# TinyRFNode84.net
KiCad netlist of a schematic drawn in EAGLE
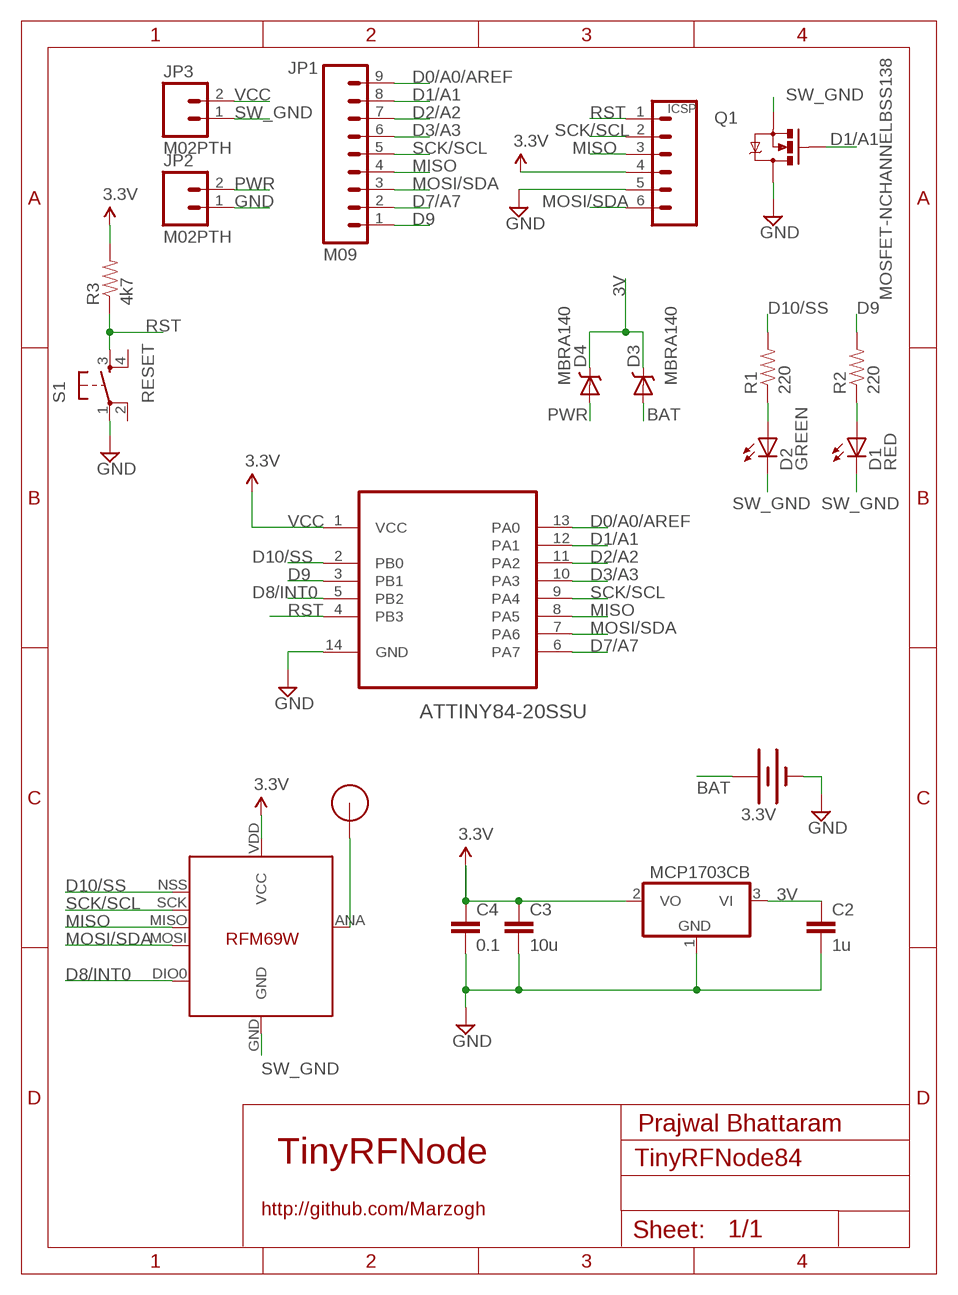
[diagram p0: schematic, sheet 1]

(export (version "E")
  (design (tool "Eeschema 10.0.6"))
  (components
    (comp (ref "BAT1")
      (value "3.3V")
      (footprint "eagle-import:BATTCON_12MM")
      (libsource (lib "eagle-import") (part "BATTERY12MM"))
    )
    (comp (ref "C2")
      (value "1u")
      (footprint "eagle-import:0603-CAP")
      (libsource (lib "eagle-import") (part "CAP0603-CAP"))
    )
    (comp (ref "C3")
      (value "10u")
      (footprint "eagle-import:0805-CAP")
      (libsource (lib "eagle-import") (part "CAP0805-CAP"))
    )
    (comp (ref "C4")
      (value "0.1")
      (footprint "eagle-import:0603-CAP")
      (libsource (lib "eagle-import") (part "CAP0603-CAP"))
    )
    (comp (ref "D1")
      (value "RED")
      (footprint "eagle-import:LED-0603")
      (libsource (lib "eagle-import") (part "LED-RED0603"))
    )
    (comp (ref "D2")
      (value "GREEN")
      (footprint "eagle-import:LED-0603")
      (libsource (lib "eagle-import") (part "LED-GREEN0603"))
    )
    (comp (ref "D3")
      (value "MBRA140")
      (footprint "eagle-import:SMA-DIODE")
      (libsource (lib "eagle-import") (part "DIODE-SCHOTTKY-MBRA140"))
    )
    (comp (ref "D4")
      (value "MBRA140")
      (footprint "eagle-import:SMA-DIODE")
      (libsource (lib "eagle-import") (part "DIODE-SCHOTTKY-MBRA140"))
    )
    (comp (ref "IC3")
      (value "MCP1703CB")
      (footprint "eagle-import:SOT23")
      (libsource (lib "eagle-import") (part "MCP1703CB"))
    )
    (comp (ref "ICSP")
      (value "ICSP")
      (footprint "eagle-import:1X06_NO_SILK")
      (libsource (lib "eagle-import") (part "M06NO_SILK"))
    )
    (comp (ref "JP1")
      (value "M09")
      (footprint "eagle-import:1X09")
      (libsource (lib "eagle-import") (part "M09"))
    )
    (comp (ref "JP2")
      (value "M02PTH")
      (footprint "eagle-import:1X02")
      (libsource (lib "eagle-import") (part "M02PTH"))
    )
    (comp (ref "JP3")
      (value "M02PTH")
      (footprint "eagle-import:1X02")
      (libsource (lib "eagle-import") (part "M02PTH"))
    )
    (comp (ref "Q1")
      (value "MOSFET-NCHANNELBSS138")
      (footprint "eagle-import:SOT23")
      (libsource (lib "eagle-import") (part "MOSFET-NCHANNELBSS138"))
    )
    (comp (ref "R1")
      (value "220")
      (footprint "eagle-import:0603-RES")
      (libsource (lib "eagle-import") (part "RESISTOR0603-RES"))
    )
    (comp (ref "R2")
      (value "220")
      (footprint "eagle-import:0603-RES")
      (libsource (lib "eagle-import") (part "RESISTOR0603-RES"))
    )
    (comp (ref "R3")
      (value "4k7")
      (footprint "eagle-import:0402-RES")
      (libsource (lib "eagle-import") (part "RESISTOR0402-RES"))
    )
    (comp (ref "S1")
      (value "RESET")
      (footprint "eagle-import:TACTILE-SWITCH-SMD")
      (libsource (lib "eagle-import") (part "TAC_SWITCHSMD"))
    )
    (comp (ref "U$1")
      (value "RFM12B_ANTENNA")
      (footprint "eagle-import:RFM12B-ANTENNA")
      (libsource (lib "eagle-import") (part "RFM12B_ANTENNA"))
    )
    (comp (ref "U$5")
      (value "RFM69")
      (footprint "eagle-import:RFM69W-MINPADS")
      (libsource (lib "eagle-import") (part "RFM69"))
    )
    (comp (ref "U1")
      (value "ATTINY84-20SSU")
      (footprint "eagle-import:SOIC127P600X175-14N")
      (libsource (lib "eagle-import") (part "ATTINY84-20SSU"))
    )
  )
  (nets
    (net (code "1") (name "/3V") (class "Default")
      (node (ref "C2") (pin "1") (pinfunction "1_1") (pintype "passive"))
      (node (ref "D3") (pin "C") (pinfunction "C_C") (pintype "passive"))
      (node (ref "D4") (pin "C") (pinfunction "C_C") (pintype "passive"))
      (node (ref "IC3") (pin "3") (pinfunction "VI_3") (pintype "input"))
    )
    (net (code "2") (name "/BAT") (class "Default")
      (node (ref "BAT1") (pin "PWR@1") (pinfunction "+_PWR@1") (pintype "power_in"))
      (node (ref "D3") (pin "A") (pinfunction "A_A") (pintype "passive"))
    )
    (net (code "3") (name "/D0{slash}A0{slash}AREF") (class "Default")
      (node (ref "JP1") (pin "9") (pinfunction "9_9") (pintype "passive"))
      (node (ref "U1") (pin "13") (pinfunction "PA0_13") (pintype "bidirectional"))
    )
    (net (code "4") (name "/D1{slash}A1") (class "Default")
      (node (ref "JP1") (pin "8") (pinfunction "8_8") (pintype "passive"))
      (node (ref "Q1") (pin "1") (pinfunction "G_1") (pintype "passive"))
      (node (ref "U1") (pin "12") (pinfunction "PA1_12") (pintype "bidirectional"))
    )
    (net (code "5") (name "/D2{slash}A2") (class "Default")
      (node (ref "JP1") (pin "7") (pinfunction "7_7") (pintype "passive"))
      (node (ref "U1") (pin "11") (pinfunction "PA2_11") (pintype "bidirectional"))
    )
    (net (code "6") (name "/D3{slash}A3") (class "Default")
      (node (ref "JP1") (pin "6") (pinfunction "6_6") (pintype "passive"))
      (node (ref "U1") (pin "10") (pinfunction "PA3_10") (pintype "bidirectional"))
    )
    (net (code "7") (name "/D7{slash}A7") (class "Default")
      (node (ref "JP1") (pin "2") (pinfunction "2_2") (pintype "passive"))
      (node (ref "U1") (pin "6") (pinfunction "PA7_6") (pintype "bidirectional"))
    )
    (net (code "8") (name "/D8{slash}INT0") (class "Default")
      (node (ref "U$5") (pin "DIO0") (pinfunction "DIO0_DIO0") (pintype "open_collector"))
      (node (ref "U1") (pin "5") (pinfunction "PB2_5") (pintype "bidirectional"))
    )
    (net (code "9") (name "/D9") (class "Default")
      (node (ref "JP1") (pin "1") (pinfunction "1_1") (pintype "passive"))
      (node (ref "R2") (pin "2") (pinfunction "2_2") (pintype "passive"))
      (node (ref "U1") (pin "3") (pinfunction "PB1_3") (pintype "bidirectional"))
    )
    (net (code "10") (name "/D10{slash}SS") (class "Default")
      (node (ref "R1") (pin "2") (pinfunction "2_2") (pintype "passive"))
      (node (ref "U$5") (pin "NSS") (pinfunction "SEL_NSS") (pintype "input"))
      (node (ref "U1") (pin "2") (pinfunction "PB0_2") (pintype "bidirectional"))
    )
    (net (code "11") (name "/MISO") (class "Default")
      (node (ref "ICSP") (pin "3") (pinfunction "3_3") (pintype "passive"))
      (node (ref "JP1") (pin "4") (pinfunction "4_4") (pintype "passive"))
      (node (ref "U$5") (pin "MISO") (pinfunction "MISO_MISO") (pintype "input"))
      (node (ref "U1") (pin "8") (pinfunction "PA5_8") (pintype "bidirectional"))
    )
    (net (code "12") (name "/MOSI{slash}SDA") (class "Default")
      (node (ref "ICSP") (pin "6") (pinfunction "6_6") (pintype "passive"))
      (node (ref "JP1") (pin "3") (pinfunction "3_3") (pintype "passive"))
      (node (ref "U$5") (pin "MOSI") (pinfunction "MOSI_MOSI") (pintype "output"))
      (node (ref "U1") (pin "7") (pinfunction "PA6_7") (pintype "bidirectional"))
    )
    (net (code "13") (name "/PWR") (class "Default")
      (node (ref "D4") (pin "A") (pinfunction "A_A") (pintype "passive"))
      (node (ref "JP2") (pin "2") (pinfunction "2_2") (pintype "passive"))
    )
    (net (code "14") (name "/RST") (class "Default")
      (node (ref "ICSP") (pin "1") (pinfunction "1_1") (pintype "passive"))
      (node (ref "R3") (pin "1") (pinfunction "1_1") (pintype "passive"))
      (node (ref "S1") (pin "3") (pinfunction "3_3") (pintype "passive"))
      (node (ref "U1") (pin "4") (pinfunction "PB3_4") (pintype "bidirectional"))
    )
    (net (code "15") (name "/SCK{slash}SCL") (class "Default")
      (node (ref "ICSP") (pin "2") (pinfunction "2_2") (pintype "passive"))
      (node (ref "JP1") (pin "5") (pinfunction "5_5") (pintype "passive"))
      (node (ref "U$5") (pin "SCK") (pinfunction "SCK_SCK") (pintype "input"))
      (node (ref "U1") (pin "9") (pinfunction "PA4_9") (pintype "bidirectional"))
    )
    (net (code "16") (name "/SW_GND") (class "Default")
      (node (ref "D1") (pin "C") (pinfunction "C_C") (pintype "passive"))
      (node (ref "D2") (pin "C") (pinfunction "C_C") (pintype "passive"))
      (node (ref "JP3") (pin "1") (pinfunction "1_1") (pintype "passive"))
      (node (ref "Q1") (pin "2") (pinfunction "S_2") (pintype "passive"))
      (node (ref "U$5") (pin "GND") (pinfunction "GND_GND") (pintype "power_in"))
    )
    (net (code "17") (name "3.3V") (class "Default")
      (node (ref "C3") (pin "1") (pinfunction "1_1") (pintype "passive"))
      (node (ref "C4") (pin "1") (pinfunction "1_1") (pintype "passive"))
      (node (ref "IC3") (pin "2") (pinfunction "VO_2") (pintype "passive"))
      (node (ref "ICSP") (pin "4") (pinfunction "4_4") (pintype "passive"))
      (node (ref "JP3") (pin "2") (pinfunction "2_2") (pintype "passive"))
      (node (ref "R3") (pin "2") (pinfunction "2_2") (pintype "passive"))
      (node (ref "U$5") (pin "VDD") (pinfunction "VCC_VDD") (pintype "power_in"))
      (node (ref "U1") (pin "1") (pinfunction "VCC_1") (pintype "power_in"))
    )
    (net (code "18") (name "GND") (class "Default")
      (node (ref "BAT1") (pin "GND") (pinfunction "-_GND") (pintype "power_in"))
      (node (ref "C2") (pin "2") (pinfunction "2_2") (pintype "passive"))
      (node (ref "C3") (pin "2") (pinfunction "2_2") (pintype "passive"))
      (node (ref "C4") (pin "2") (pinfunction "2_2") (pintype "passive"))
      (node (ref "IC3") (pin "1") (pinfunction "GND_1") (pintype "passive"))
      (node (ref "ICSP") (pin "5") (pinfunction "5_5") (pintype "passive"))
      (node (ref "JP2") (pin "1") (pinfunction "1_1") (pintype "passive"))
      (node (ref "Q1") (pin "3") (pinfunction "D_3") (pintype "passive"))
      (node (ref "S1") (pin "1") (pinfunction "1_1") (pintype "passive"))
      (node (ref "U1") (pin "14") (pinfunction "GND_14") (pintype "passive"))
    )
    (net (code "19") (name "Net-(D1-PadA)") (class "Default")
      (node (ref "D1") (pin "A") (pinfunction "A_A") (pintype "passive"))
      (node (ref "R2") (pin "1") (pinfunction "1_1") (pintype "passive"))
    )
    (net (code "20") (name "Net-(D2-PadA)") (class "Default")
      (node (ref "D2") (pin "A") (pinfunction "A_A") (pintype "passive"))
      (node (ref "R1") (pin "1") (pinfunction "1_1") (pintype "passive"))
    )
    (net (code "21") (name "Net-(U$1-1)") (class "Default")
      (node (ref "U$1") (pin "P$1") (pinfunction "1_P$1") (pintype "bidirectional"))
      (node (ref "U$5") (pin "ANA") (pinfunction "ANT_ANA") (pintype "passive"))
    )
    (net (code "22") (name "unconnected-(S1-Pad2)") (class "Default")
      (node (ref "S1") (pin "2") (pinfunction "2_2") (pintype "passive"))
    )
    (net (code "23") (name "unconnected-(S1-Pad4)") (class "Default")
      (node (ref "S1") (pin "4") (pinfunction "4_4") (pintype "passive"))
    )
  )
)
